# 04-USB_POWER.net
KiCad netlist of a schematic drawn in Altium Designer
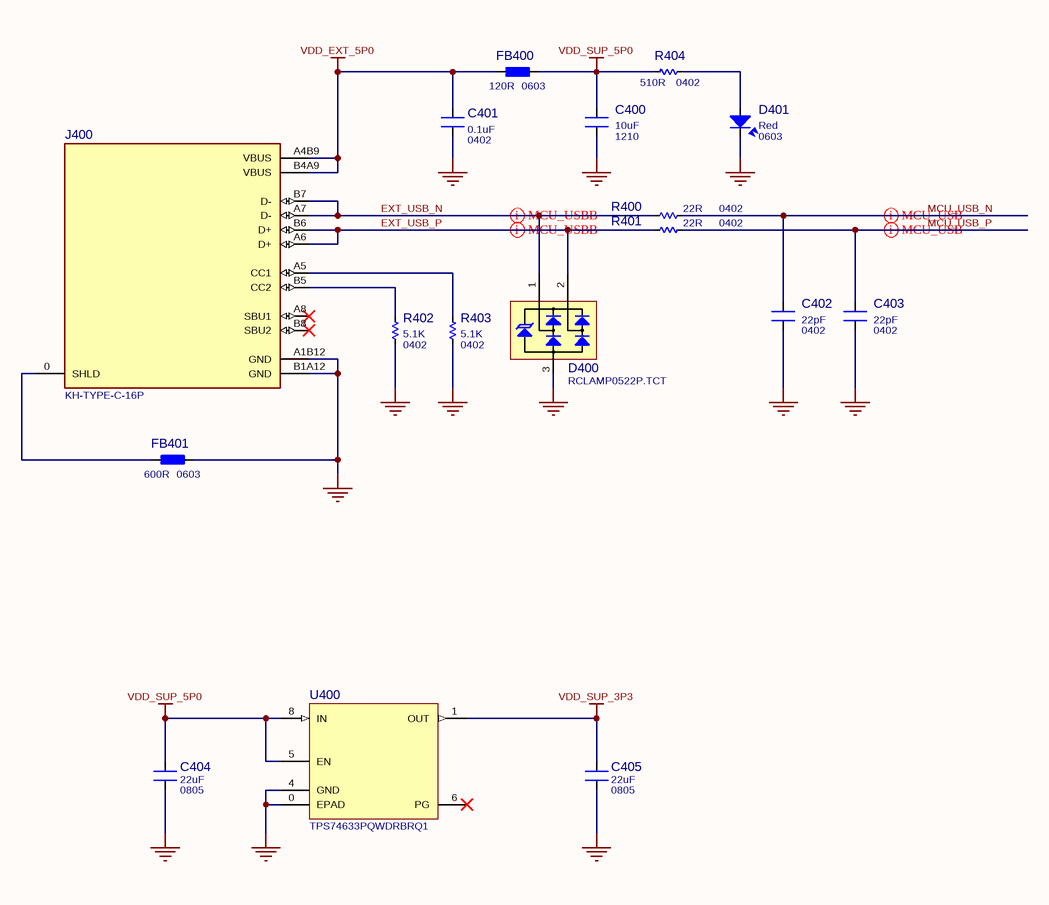
[diagram p0: 04-USB_POWER.SchDoc]

(export (version "E")
  (design (tool "Eeschema 10.0.6"))
  (components
    (comp (ref "C400")
      (value "10uF")
      (footprint "CAP_C_1210")
      (description "Ceramic Capacitor SMD 1210 10uF ±10% 25V")
      (fields
        (field (name "TOLERANCE") "±10%")
        (field (name "MANUFACTURER") "Samsung")
        (field (name "PACKAGE") "1210")
      )
      (libsource (lib "AS50") (part "Cap"))
    )
    (comp (ref "C401")
      (value "0.1uF")
      (footprint "CAP_C_0402")
      (description "Ceramic Capacitor SMD 0402 100nF ±10% 16V")
      (fields
        (field (name "TOLERANCE") "±10%")
        (field (name "MANUFACTURER") "Samsung")
        (field (name "PACKAGE") "0402")
      )
      (libsource (lib "AS50") (part "Cap"))
    )
    (comp (ref "C402")
      (value "22pF")
      (footprint "CAP_C_0402")
      (description "Ceramic Capacitor SMD 0402 22pF ±5% 50V")
      (fields
        (field (name "TOLERANCE") "±5%")
        (field (name "MANUFACTURER") "FH(Guangdong Fenghua Advanced Tech)")
        (field (name "PACKAGE") "0402")
      )
      (libsource (lib "AS50") (part "Cap"))
    )
    (comp (ref "C403")
      (value "22pF")
      (footprint "CAP_C_0402")
      (description "Ceramic Capacitor SMD 0402 22pF ±5% 50V")
      (fields
        (field (name "TOLERANCE") "±5%")
        (field (name "MANUFACTURER") "FH(Guangdong Fenghua Advanced Tech)")
        (field (name "PACKAGE") "0402")
      )
      (libsource (lib "AS50") (part "Cap"))
    )
    (comp (ref "C404")
      (value "22uF")
      (footprint "CAP_C_0805")
      (description "Ceramic Capacitor SMD 0805 22uF ±20% 10V")
      (fields
        (field (name "TOLERANCE") "±20%")
        (field (name "MANUFACTURER") "Samsung")
        (field (name "PACKAGE") "0805")
      )
      (libsource (lib "AS50") (part "Cap"))
    )
    (comp (ref "C405")
      (value "22uF")
      (footprint "CAP_C_0805")
      (description "Ceramic Capacitor SMD 0805 22uF ±20% 10V")
      (fields
        (field (name "TOLERANCE") "±20%")
        (field (name "MANUFACTURER") "Samsung")
        (field (name "PACKAGE") "0805")
      )
      (libsource (lib "AS50") (part "Cap"))
    )
    (comp (ref "D400")
      (value "RCLAMP0522P.TCT")
      (footprint "Diodes:SLP1610P4")
      (description "15V Clamp 5A (8/20µs) Ipp TVS Diode Surface Mount SLP1610P4")
      (fields
        (field (name "MANUFACTURER") "Semtech")
        (field (name "MANUFACTURER PART NUMBER") "RCLAMP0522P.TCT")
      )
      (libsource (lib "AS50") (part "RCLAMP0522P.TCT"))
    )
    (comp (ref "D401")
      (value "LED")
      (footprint "LED-SMD-0603-RED")
      (description "Red 615~630nm 1.9~2.2V 0603 Light Emitting Diodes (LED) RoHS")
      (fields
        (field (name "MANUFACTURER") "Hubei KENTO Elec")
        (field (name "MANUFACTURER PART NUMBER") "KT-0603R")
        (field (name "COLOR") "Red")
        (field (name "PACKAGE") "0603")
      )
      (libsource (lib "AS50") (part "LED"))
    )
    (comp (ref "FB400")
      (value "120R")
      (footprint "Inductors:IND_C_0603")
      (description "Ferrite bead SMD 0603 120Ω ±25% @ 100MHz DCR=0.03Ω 3A")
      (fields
        (field (name "MANUFACTURER") "Murata Electronics")
        (field (name "MANUFACTURER PART NUMBER") "BLM18KG121TH1D")
        (field (name "PACKAGE") "0603")
      )
      (libsource (lib "AS50") (part "Ferrite bead"))
    )
    (comp (ref "FB401")
      (value "600R")
      (footprint "Inductors:IND_C_0603")
      (description "Ferrite bead SMD 0603 600Ω ±25% @ 100MHz DCR=0.15Ω 1.3A")
      (fields
        (field (name "MANUFACTURER") "Murata Electronics")
        (field (name "MANUFACTURER PART NUMBER") "BLM18KG601SN1D")
        (field (name "PACKAGE") "0603")
      )
      (libsource (lib "AS50") (part "Ferrite bead"))
    )
    (comp (ref "J400")
      (value "USB_C-16P")
      (footprint "USB_C_F_16P_SMD")
      (description "3A 16-pin Female -40℃~+85℃ Type-C SMD USB Connectors")
      (fields
        (field (name "MANUFACTURER") "Shenzhen Kinghelm Elec")
        (field (name "MANUFACTURER PART NUMBER") "KH-TYPE-C-16P")
      )
      (libsource (lib "AS50") (part "USB_C-16P"))
    )
    (comp (ref "R400")
      (value "22R")
      (footprint "RES_C_0402")
      (description "Resistor SMD 0402 22R ±1% 1/16W")
      (fields (field (name "PACKAGE") "0402") (field (name "TOLERANCE") "±1%") (field (name "VOLTAGE") "50V"))
      (libsource (lib "AS50") (part "Res"))
    )
    (comp (ref "R401")
      (value "22R")
      (footprint "RES_C_0402")
      (description "Resistor SMD 0402 22R ±1% 1/16W")
      (fields (field (name "PACKAGE") "0402") (field (name "TOLERANCE") "±1%") (field (name "VOLTAGE") "50V"))
      (libsource (lib "AS50") (part "Res"))
    )
    (comp (ref "R402")
      (value "5.1K")
      (footprint "RES_C_0402")
      (description "Resistor SMD 0402 5.1K ±1% 1/16W")
      (fields (field (name "PACKAGE") "0402") (field (name "TOLERANCE") "±1%") (field (name "VOLTAGE") "50V"))
      (libsource (lib "AS50") (part "Res"))
    )
    (comp (ref "R403")
      (value "5.1K")
      (footprint "RES_C_0402")
      (description "Resistor SMD 0402 5.1K ±1% 1/16W")
      (fields (field (name "PACKAGE") "0402") (field (name "TOLERANCE") "±1%") (field (name "VOLTAGE") "50V"))
      (libsource (lib "AS50") (part "Res"))
    )
    (comp (ref "R404")
      (value "510R")
      (footprint "RES_C_0402")
      (description "Resistor SMD 0402 510R ±1% 1/16W")
      (fields (field (name "PACKAGE") "0402") (field (name "TOLERANCE") "±1%") (field (name "VOLTAGE") "50V"))
      (libsource (lib "AS50") (part "Res"))
    )
    (comp (ref "U400")
      (value "TPS74633PQWDRBRQ1")
      (footprint "SON65P300X100_HS-9N")
      (fields
        (field (name "MANUFACTURER") "Texas Instruments")
        (field (name "MANUFACTURER PART NUMBER") "TPS74633PQWDRBRQ1")
      )
      (libsource (lib "AS50") (part "TPS746xxPQWDRBRQ1"))
    )
  )
  (nets
    (net (code "1") (name "/EXT_USB_N") (class "Default")
      (node (ref "D400") (pin "1") (pinfunction "DM_1") (pintype "passive"))
      (node (ref "J400") (pin "A7") (pinfunction "D-_A7") (pintype "bidirectional"))
      (node (ref "J400") (pin "B7") (pinfunction "D-_B7") (pintype "bidirectional"))
      (node (ref "R400") (pin "1") (pinfunction "1_1") (pintype "passive"))
    )
    (net (code "2") (name "/EXT_USB_P") (class "Default")
      (node (ref "D400") (pin "2") (pinfunction "DP_2") (pintype "passive"))
      (node (ref "J400") (pin "A6") (pinfunction "D+_A6") (pintype "bidirectional"))
      (node (ref "J400") (pin "B6") (pinfunction "D+_B6") (pintype "bidirectional"))
      (node (ref "R401") (pin "1") (pinfunction "1_1") (pintype "passive"))
    )
    (net (code "3") (name "/MCU_USB_N") (class "Default")
      (node (ref "C402") (pin "1") (pinfunction "1_1") (pintype "passive"))
      (node (ref "R400") (pin "2") (pinfunction "2_2") (pintype "passive"))
    )
    (net (code "4") (name "/MCU_USB_P") (class "Default")
      (node (ref "C403") (pin "1") (pinfunction "1_1") (pintype "passive"))
      (node (ref "R401") (pin "2") (pinfunction "2_2") (pintype "passive"))
    )
    (net (code "5") (name "GND") (class "Default")
      (node (ref "C400") (pin "1") (pinfunction "1_1") (pintype "passive"))
      (node (ref "C401") (pin "1") (pinfunction "1_1") (pintype "passive"))
      (node (ref "C402") (pin "2") (pinfunction "2_2") (pintype "passive"))
      (node (ref "C403") (pin "2") (pinfunction "2_2") (pintype "passive"))
      (node (ref "C404") (pin "1") (pinfunction "1_1") (pintype "passive"))
      (node (ref "C405") (pin "1") (pinfunction "1_1") (pintype "passive"))
      (node (ref "D400") (pin "3") (pinfunction "GND_3") (pintype "passive"))
      (node (ref "D401") (pin "2") (pinfunction "2_2") (pintype "passive"))
      (node (ref "FB401") (pin "1") (pinfunction "1_1") (pintype "passive"))
      (node (ref "J400") (pin "A1B12") (pinfunction "GND_A1B12") (pintype "passive"))
      (node (ref "J400") (pin "B1A12") (pinfunction "GND_B1A12") (pintype "passive"))
      (node (ref "R402") (pin "2") (pinfunction "2_2") (pintype "passive"))
      (node (ref "R403") (pin "2") (pinfunction "2_2") (pintype "passive"))
      (node (ref "U400") (pin "0") (pinfunction "EPAD_0") (pintype "passive"))
      (node (ref "U400") (pin "4") (pinfunction "GND_4") (pintype "power_in"))
    )
    (net (code "6") (name "Net-(D401-Pad1)") (class "Default")
      (node (ref "D401") (pin "1") (pinfunction "1_1") (pintype "passive"))
      (node (ref "R404") (pin "2") (pinfunction "2_2") (pintype "passive"))
    )
    (net (code "7") (name "Net-(J400-CC1)") (class "Default")
      (node (ref "J400") (pin "A5") (pinfunction "CC1_A5") (pintype "bidirectional"))
      (node (ref "R403") (pin "1") (pinfunction "1_1") (pintype "passive"))
    )
    (net (code "8") (name "Net-(J400-CC2)") (class "Default")
      (node (ref "J400") (pin "B5") (pinfunction "CC2_B5") (pintype "bidirectional"))
      (node (ref "R402") (pin "1") (pinfunction "1_1") (pintype "passive"))
    )
    (net (code "9") (name "Net-(J400-SHLD)") (class "Default")
      (node (ref "FB401") (pin "2") (pinfunction "2_2") (pintype "passive"))
      (node (ref "J400") (pin "0") (pinfunction "SHLD_0") (pintype "passive"))
    )
    (net (code "10") (name "VDD_EXT_5P0") (class "Default")
      (node (ref "C401") (pin "2") (pinfunction "2_2") (pintype "passive"))
      (node (ref "FB400") (pin "2") (pinfunction "2_2") (pintype "passive"))
      (node (ref "J400") (pin "A4B9") (pinfunction "VBUS_A4B9") (pintype "power_in"))
      (node (ref "J400") (pin "B4A9") (pinfunction "VBUS_B4A9") (pintype "power_in"))
    )
    (net (code "11") (name "VDD_SUP_3P3") (class "Default")
      (node (ref "C405") (pin "2") (pinfunction "2_2") (pintype "passive"))
      (node (ref "U400") (pin "1") (pinfunction "OUT_1") (pintype "output"))
    )
    (net (code "12") (name "VDD_SUP_5P0") (class "Default")
      (node (ref "C400") (pin "2") (pinfunction "2_2") (pintype "passive"))
      (node (ref "C404") (pin "2") (pinfunction "2_2") (pintype "passive"))
      (node (ref "FB400") (pin "1") (pinfunction "1_1") (pintype "passive"))
      (node (ref "R404") (pin "1") (pinfunction "1_1") (pintype "passive"))
      (node (ref "U400") (pin "5") (pinfunction "EN_5") (pintype "passive"))
      (node (ref "U400") (pin "8") (pinfunction "IN_8") (pintype "input"))
    )
    (net (code "13") (name "unconnected-(J400-SBU1-PadA8)") (class "Default")
      (node (ref "J400") (pin "A8") (pinfunction "SBU1_A8") (pintype "bidirectional+no_connect"))
    )
    (net (code "14") (name "unconnected-(J400-SBU2-PadB8)") (class "Default")
      (node (ref "J400") (pin "B8") (pinfunction "SBU2_B8") (pintype "bidirectional+no_connect"))
    )
    (net (code "15") (name "unconnected-(U400-PG-Pad6)") (class "Default")
      (node (ref "U400") (pin "6") (pinfunction "PG_6") (pintype "passive+no_connect"))
    )
  )
)
